# keyboard_5keys_board.net
KiCad netlist of a schematic drawn in EAGLE
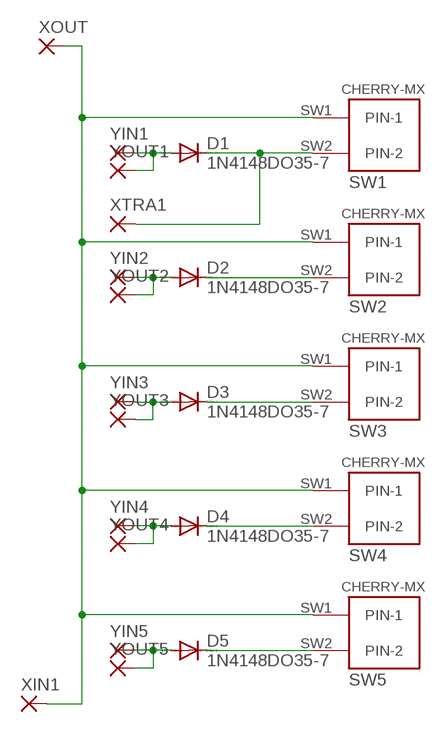
[diagram p0: schematic, sheet 1]

(export (version "E")
  (design (tool "Eeschema 10.0.6"))
  (components
    (comp (ref "D1")
      (value "1N4148DO35-7")
      (footprint "eagle-import:DO35-7")
      (libsource (lib "eagle-import") (part "1N4148DO35-7"))
    )
    (comp (ref "D2")
      (value "1N4148DO35-7")
      (footprint "eagle-import:DO35-7")
      (libsource (lib "eagle-import") (part "1N4148DO35-7"))
    )
    (comp (ref "D3")
      (value "1N4148DO35-7")
      (footprint "eagle-import:DO35-7")
      (libsource (lib "eagle-import") (part "1N4148DO35-7"))
    )
    (comp (ref "D4")
      (value "1N4148DO35-7")
      (footprint "eagle-import:DO35-7")
      (libsource (lib "eagle-import") (part "1N4148DO35-7"))
    )
    (comp (ref "D5")
      (value "1N4148DO35-7")
      (footprint "eagle-import:DO35-7")
      (libsource (lib "eagle-import") (part "1N4148DO35-7"))
    )
    (comp (ref "SW1")
      (value "CHERRY-MX")
      (footprint "eagle-import:CHERRY-MX")
      (libsource (lib "eagle-import") (part "CHERRY-MX"))
    )
    (comp (ref "SW2")
      (value "CHERRY-MX")
      (footprint "eagle-import:CHERRY-MX")
      (libsource (lib "eagle-import") (part "CHERRY-MX"))
    )
    (comp (ref "SW3")
      (value "CHERRY-MX")
      (footprint "eagle-import:CHERRY-MX")
      (libsource (lib "eagle-import") (part "CHERRY-MX"))
    )
    (comp (ref "SW4")
      (value "CHERRY-MX")
      (footprint "eagle-import:CHERRY-MX")
      (libsource (lib "eagle-import") (part "CHERRY-MX"))
    )
    (comp (ref "SW5")
      (value "CHERRY-MX")
      (footprint "eagle-import:CHERRY-MX")
      (libsource (lib "eagle-import") (part "CHERRY-MX"))
    )
    (comp (ref "XIN1")
      (value "1,6/0,8")
      (footprint "eagle-import:1,6_0,8")
      (libsource (lib "eagle-import") (part "1,6/0,8"))
    )
    (comp (ref "XOUT")
      (value "1,6/0,8")
      (footprint "eagle-import:1,6_0,8")
      (libsource (lib "eagle-import") (part "1,6/0,8"))
    )
    (comp (ref "XTRA1")
      (value "1,6/0,8")
      (footprint "eagle-import:1,6_0,8")
      (libsource (lib "eagle-import") (part "1,6/0,8"))
    )
    (comp (ref "YIN1")
      (value "1,6/0,8")
      (footprint "eagle-import:1,6_0,8")
      (libsource (lib "eagle-import") (part "1,6/0,8"))
    )
    (comp (ref "YIN2")
      (value "1,6/0,8")
      (footprint "eagle-import:1,6_0,8")
      (libsource (lib "eagle-import") (part "1,6/0,8"))
    )
    (comp (ref "YIN3")
      (value "1,6/0,8")
      (footprint "eagle-import:1,6_0,8")
      (libsource (lib "eagle-import") (part "1,6/0,8"))
    )
    (comp (ref "YIN4")
      (value "1,6/0,8")
      (footprint "eagle-import:1,6_0,8")
      (libsource (lib "eagle-import") (part "1,6/0,8"))
    )
    (comp (ref "YIN5")
      (value "1,6/0,8")
      (footprint "eagle-import:1,6_0,8")
      (libsource (lib "eagle-import") (part "1,6/0,8"))
    )
    (comp (ref "YOUT1")
      (value "1,6/0,8")
      (footprint "eagle-import:1,6_0,8")
      (libsource (lib "eagle-import") (part "1,6/0,8"))
    )
    (comp (ref "YOUT2")
      (value "1,6/0,8")
      (footprint "eagle-import:1,6_0,8")
      (libsource (lib "eagle-import") (part "1,6/0,8"))
    )
    (comp (ref "YOUT3")
      (value "1,6/0,8")
      (footprint "eagle-import:1,6_0,8")
      (libsource (lib "eagle-import") (part "1,6/0,8"))
    )
    (comp (ref "YOUT4")
      (value "1,6/0,8")
      (footprint "eagle-import:1,6_0,8")
      (libsource (lib "eagle-import") (part "1,6/0,8"))
    )
    (comp (ref "YOUT5")
      (value "1,6/0,8")
      (footprint "eagle-import:1,6_0,8")
      (libsource (lib "eagle-import") (part "1,6/0,8"))
    )
  )
  (nets
    (net (code "1") (name "Net-(SW1-PIN-1)") (class "Default")
      (node (ref "SW1") (pin "SW1") (pinfunction "PIN-1_SW1") (pintype "bidirectional"))
      (node (ref "SW2") (pin "SW1") (pinfunction "PIN-1_SW1") (pintype "bidirectional"))
      (node (ref "SW3") (pin "SW1") (pinfunction "PIN-1_SW1") (pintype "bidirectional"))
      (node (ref "SW4") (pin "SW1") (pinfunction "PIN-1_SW1") (pintype "bidirectional"))
      (node (ref "SW5") (pin "SW1") (pinfunction "PIN-1_SW1") (pintype "bidirectional"))
      (node (ref "XIN1") (pin "1") (pinfunction "P_1") (pintype "passive"))
      (node (ref "XOUT") (pin "1") (pinfunction "P_1") (pintype "passive"))
    )
    (net (code "2") (name "Net-(SW1-PIN-2)") (class "Default")
      (node (ref "D1") (pin "C") (pinfunction "C_C") (pintype "passive"))
      (node (ref "SW1") (pin "SW2") (pinfunction "PIN-2_SW2") (pintype "bidirectional"))
      (node (ref "XTRA1") (pin "1") (pinfunction "P_1") (pintype "passive"))
    )
    (net (code "3") (name "Net-(SW2-PIN-2)") (class "Default")
      (node (ref "D2") (pin "C") (pinfunction "C_C") (pintype "passive"))
      (node (ref "SW2") (pin "SW2") (pinfunction "PIN-2_SW2") (pintype "bidirectional"))
    )
    (net (code "4") (name "Net-(SW3-PIN-2)") (class "Default")
      (node (ref "D3") (pin "C") (pinfunction "C_C") (pintype "passive"))
      (node (ref "SW3") (pin "SW2") (pinfunction "PIN-2_SW2") (pintype "bidirectional"))
    )
    (net (code "5") (name "Net-(SW4-PIN-2)") (class "Default")
      (node (ref "D4") (pin "C") (pinfunction "C_C") (pintype "passive"))
      (node (ref "SW4") (pin "SW2") (pinfunction "PIN-2_SW2") (pintype "bidirectional"))
    )
    (net (code "6") (name "Net-(SW5-PIN-2)") (class "Default")
      (node (ref "D5") (pin "C") (pinfunction "C_C") (pintype "passive"))
      (node (ref "SW5") (pin "SW2") (pinfunction "PIN-2_SW2") (pintype "bidirectional"))
    )
    (net (code "7") (name "Net-(YIN1-P)") (class "Default")
      (node (ref "D1") (pin "A") (pinfunction "A_A") (pintype "passive"))
      (node (ref "YIN1") (pin "1") (pinfunction "P_1") (pintype "passive"))
      (node (ref "YOUT1") (pin "1") (pinfunction "P_1") (pintype "passive"))
    )
    (net (code "8") (name "Net-(YIN2-P)") (class "Default")
      (node (ref "D2") (pin "A") (pinfunction "A_A") (pintype "passive"))
      (node (ref "YIN2") (pin "1") (pinfunction "P_1") (pintype "passive"))
      (node (ref "YOUT2") (pin "1") (pinfunction "P_1") (pintype "passive"))
    )
    (net (code "9") (name "Net-(YIN3-P)") (class "Default")
      (node (ref "D3") (pin "A") (pinfunction "A_A") (pintype "passive"))
      (node (ref "YIN3") (pin "1") (pinfunction "P_1") (pintype "passive"))
      (node (ref "YOUT3") (pin "1") (pinfunction "P_1") (pintype "passive"))
    )
    (net (code "10") (name "Net-(YIN4-P)") (class "Default")
      (node (ref "D4") (pin "A") (pinfunction "A_A") (pintype "passive"))
      (node (ref "YIN4") (pin "1") (pinfunction "P_1") (pintype "passive"))
      (node (ref "YOUT4") (pin "1") (pinfunction "P_1") (pintype "passive"))
    )
    (net (code "11") (name "Net-(YIN5-P)") (class "Default")
      (node (ref "D5") (pin "A") (pinfunction "A_A") (pintype "passive"))
      (node (ref "YIN5") (pin "1") (pinfunction "P_1") (pintype "passive"))
      (node (ref "YOUT5") (pin "1") (pinfunction "P_1") (pintype "passive"))
    )
  )
)
